# DRIVER_A.net
KiCad netlist of a schematic drawn in Altium Designer
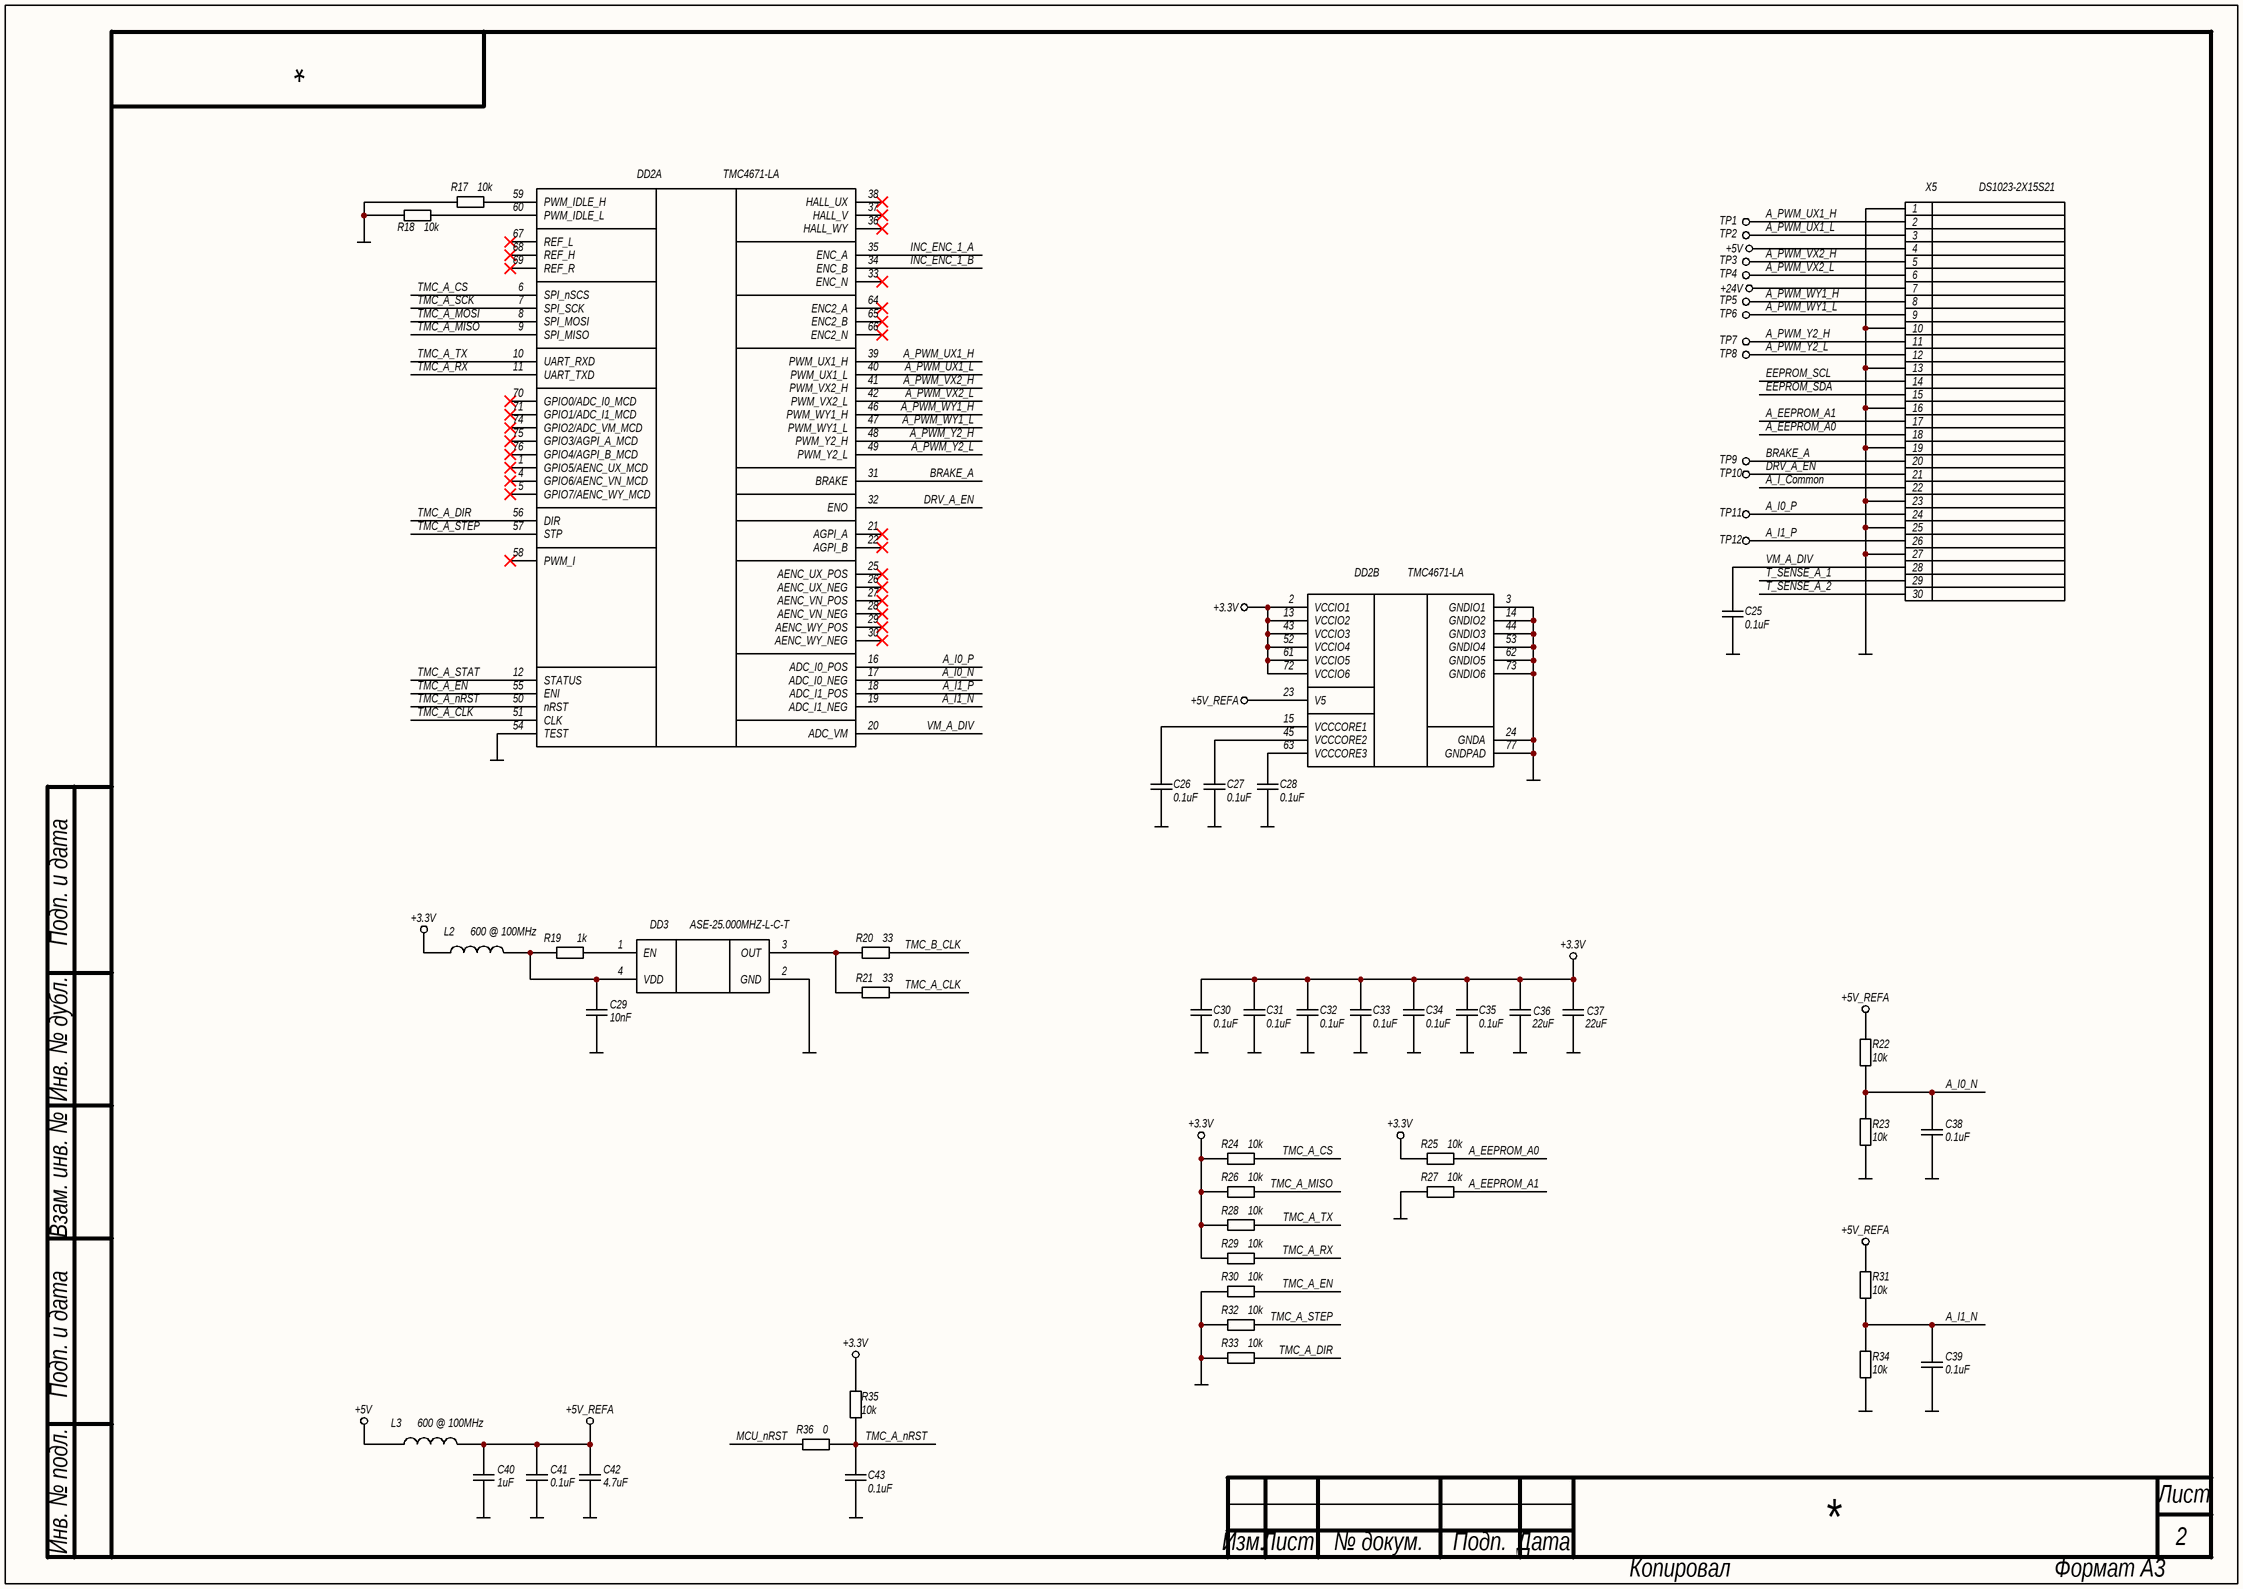
[diagram p0: DRIVER_A.SchDoc]

(export (version "E")
  (design (tool "Eeschema 10.0.6"))
  (components
    (comp (ref "C25")
      (value "0.1uF")
      (footprint "C0603N")
      (description "Конденсатор")
      (libsource (lib "Components Library") (part "CAP_FIXED"))
    )
    (comp (ref "C26")
      (value "0.1uF")
      (footprint "C0603N")
      (description "Конденсатор")
      (libsource (lib "Components Library") (part "CAP_FIXED"))
    )
    (comp (ref "C27")
      (value "0.1uF")
      (footprint "C0603N")
      (description "Конденсатор")
      (libsource (lib "Components Library") (part "CAP_FIXED"))
    )
    (comp (ref "C28")
      (value "0.1uF")
      (footprint "C0603N")
      (description "Конденсатор")
      (libsource (lib "Components Library") (part "CAP_FIXED"))
    )
    (comp (ref "C29")
      (value "10nF")
      (footprint "C0603N")
      (description "Конденсатор")
      (libsource (lib "Components Library") (part "CAP_FIXED"))
    )
    (comp (ref "C30")
      (value "0.1uF")
      (footprint "C0603N")
      (description "Конденсатор")
      (libsource (lib "Components Library") (part "CAP_FIXED"))
    )
    (comp (ref "C31")
      (value "0.1uF")
      (footprint "C0603N")
      (description "Конденсатор")
      (libsource (lib "Components Library") (part "CAP_FIXED"))
    )
    (comp (ref "C32")
      (value "0.1uF")
      (footprint "C0603N")
      (description "Конденсатор")
      (libsource (lib "Components Library") (part "CAP_FIXED"))
    )
    (comp (ref "C33")
      (value "0.1uF")
      (footprint "C0603N")
      (description "Конденсатор")
      (libsource (lib "Components Library") (part "CAP_FIXED"))
    )
    (comp (ref "C34")
      (value "0.1uF")
      (footprint "C0603N")
      (description "Конденсатор")
      (libsource (lib "Components Library") (part "CAP_FIXED"))
    )
    (comp (ref "C35")
      (value "0.1uF")
      (footprint "C0603N")
      (description "Конденсатор")
      (libsource (lib "Components Library") (part "CAP_FIXED"))
    )
    (comp (ref "C36")
      (value "22uF")
      (footprint "C0805N")
      (description "Конденсатор")
      (libsource (lib "Components Library") (part "CAP_FIXED"))
    )
    (comp (ref "C37")
      (value "22uF")
      (footprint "C0805N")
      (description "Конденсатор")
      (libsource (lib "Components Library") (part "CAP_FIXED"))
    )
    (comp (ref "C38")
      (value "0.1uF")
      (footprint "C0603N")
      (description "Конденсатор")
      (libsource (lib "Components Library") (part "CAP_FIXED"))
    )
    (comp (ref "C39")
      (value "0.1uF")
      (footprint "C0603N")
      (description "Конденсатор")
      (libsource (lib "Components Library") (part "CAP_FIXED"))
    )
    (comp (ref "C40")
      (value "1uF")
      (footprint "C0603N")
      (description "Конденсатор")
      (libsource (lib "Components Library") (part "CAP_FIXED"))
    )
    (comp (ref "C41")
      (value "0.1uF")
      (footprint "C0603N")
      (description "Конденсатор")
      (libsource (lib "Components Library") (part "CAP_FIXED"))
    )
    (comp (ref "C42")
      (value "4.7uF")
      (footprint "C0603N")
      (description "Конденсатор")
      (libsource (lib "Components Library") (part "CAP_FIXED"))
    )
    (comp (ref "C43")
      (value "0.1uF")
      (footprint "C0603N")
      (description "Конденсатор")
      (libsource (lib "Components Library") (part "CAP_FIXED"))
    )
    (comp (ref "DD2")
      (value "TMC4671-LA")
      (footprint "QFN76-EP")
      (description "Микросхема драйвер двигателя")
      (libsource (lib "Components Library") (part "TMC4671-LA"))
    )
    (comp (ref "DD3")
      (value "ASE-25.000MHZ-L-C-T")
      (footprint "ASE")
      (description "Кварцевый генератор")
      (libsource (lib "Components Library") (part "XTAL_OSC"))
    )
    (comp (ref "L2")
      (value "600 @ 100MHz")
      (footprint "FB0603N")
      (description "Фильтр ЭМП индуктивный")
      (libsource (lib "") (part "IND_FILTER_1"))
    )
    (comp (ref "L3")
      (value "600 @ 100MHz")
      (footprint "FB0603N")
      (description "Фильтр ЭМП индуктивный")
      (libsource (lib "Components Library") (part "IND_FILTER"))
    )
    (comp (ref "R17")
      (value "10k")
      (footprint "R0603N")
      (description "Резистор")
      (libsource (lib "Components Library") (part "RES_FIXED"))
    )
    (comp (ref "R18")
      (value "10k")
      (footprint "R0603N")
      (description "Резистор")
      (libsource (lib "Components Library") (part "RES_FIXED"))
    )
    (comp (ref "R19")
      (value "1k")
      (footprint "R0603N")
      (description "Резистор")
      (libsource (lib "") (part "RES_FIXED_1"))
    )
    (comp (ref "R20")
      (value "33")
      (footprint "R0603N")
      (description "Резистор")
      (libsource (lib "Components Library") (part "RES_FIXED"))
    )
    (comp (ref "R21")
      (value "33")
      (footprint "R0603N")
      (description "Резистор")
      (libsource (lib "Components Library") (part "RES_FIXED"))
    )
    (comp (ref "R22")
      (value "10k")
      (footprint "R0603N")
      (description "Резистор")
      (libsource (lib "") (part "RES_FIXED_2"))
    )
    (comp (ref "R23")
      (value "10k")
      (footprint "R0603N")
      (description "Резистор")
      (libsource (lib "") (part "RES_FIXED_2"))
    )
    (comp (ref "R24")
      (value "10k")
      (footprint "R0603N")
      (description "Резистор")
      (libsource (lib "Components Library") (part "RES_FIXED"))
    )
    (comp (ref "R25")
      (value "10k")
      (footprint "R0603N")
      (description "Резистор")
      (libsource (lib "Components Library") (part "RES_FIXED"))
    )
    (comp (ref "R26")
      (value "10k")
      (footprint "R0603N")
      (description "Резистор")
      (libsource (lib "Components Library") (part "RES_FIXED"))
    )
    (comp (ref "R27")
      (value "10k")
      (footprint "R0603N")
      (description "Резистор")
      (libsource (lib "Components Library") (part "RES_FIXED"))
    )
    (comp (ref "R28")
      (value "10k")
      (footprint "R0603N")
      (description "Резистор")
      (libsource (lib "Components Library") (part "RES_FIXED"))
    )
    (comp (ref "R29")
      (value "10k")
      (footprint "R0603N")
      (description "Резистор")
      (libsource (lib "Components Library") (part "RES_FIXED"))
    )
    (comp (ref "R30")
      (value "10k")
      (footprint "R0603N")
      (description "Резистор")
      (libsource (lib "Components Library") (part "RES_FIXED"))
    )
    (comp (ref "R31")
      (value "10k")
      (footprint "R0603N")
      (description "Резистор")
      (libsource (lib "") (part "RES_FIXED_2"))
    )
    (comp (ref "R32")
      (value "10k")
      (footprint "R0603N")
      (description "Резистор")
      (libsource (lib "Components Library") (part "RES_FIXED"))
    )
    (comp (ref "R33")
      (value "10k")
      (footprint "R0603N")
      (description "Резистор")
      (libsource (lib "Components Library") (part "RES_FIXED"))
    )
    (comp (ref "R34")
      (value "10k")
      (footprint "R0603N")
      (description "Резистор")
      (libsource (lib "") (part "RES_FIXED_2"))
    )
    (comp (ref "R35")
      (value "10k")
      (footprint "R0603N")
      (description "Резистор")
      (libsource (lib "") (part "RES_FIXED_2"))
    )
    (comp (ref "R36")
      (value "0")
      (footprint "R0603N")
      (description "Резистор")
      (libsource (lib "Components Library") (part "RES_FIXED"))
    )
    (comp (ref "TP1")
      (value "TEST_POINT")
      (footprint "TP_RPAD_0.8MM")
      (description "Контрольная точка")
      (libsource (lib "Components Library") (part "TEST_POINT"))
    )
    (comp (ref "TP2")
      (value "TEST_POINT")
      (footprint "TP_RPAD_0.8MM")
      (description "Контрольная точка")
      (libsource (lib "Components Library") (part "TEST_POINT"))
    )
    (comp (ref "TP3")
      (value "TEST_POINT")
      (footprint "TP_RPAD_0.8MM")
      (description "Контрольная точка")
      (libsource (lib "Components Library") (part "TEST_POINT"))
    )
    (comp (ref "TP4")
      (value "TEST_POINT")
      (footprint "TP_RPAD_0.8MM")
      (description "Контрольная точка")
      (libsource (lib "Components Library") (part "TEST_POINT"))
    )
    (comp (ref "TP5")
      (value "TEST_POINT")
      (footprint "TP_RPAD_0.8MM")
      (description "Контрольная точка")
      (libsource (lib "Components Library") (part "TEST_POINT"))
    )
    (comp (ref "TP6")
      (value "TEST_POINT")
      (footprint "TP_RPAD_0.8MM")
      (description "Контрольная точка")
      (libsource (lib "Components Library") (part "TEST_POINT"))
    )
    (comp (ref "TP7")
      (value "TEST_POINT")
      (footprint "TP_RPAD_0.8MM")
      (description "Контрольная точка")
      (libsource (lib "Components Library") (part "TEST_POINT"))
    )
    (comp (ref "TP8")
      (value "TEST_POINT")
      (footprint "TP_RPAD_0.8MM")
      (description "Контрольная точка")
      (libsource (lib "Components Library") (part "TEST_POINT"))
    )
    (comp (ref "TP9")
      (value "TEST_POINT")
      (footprint "TP_RPAD_0.8MM")
      (description "Контрольная точка")
      (libsource (lib "Components Library") (part "TEST_POINT"))
    )
    (comp (ref "TP10")
      (value "TEST_POINT")
      (footprint "TP_RPAD_0.8MM")
      (description "Контрольная точка")
      (libsource (lib "Components Library") (part "TEST_POINT"))
    )
    (comp (ref "TP11")
      (value "TEST_POINT")
      (footprint "TP_RPAD_0.8MM")
      (description "Контрольная точка")
      (libsource (lib "Components Library") (part "TEST_POINT"))
    )
    (comp (ref "TP12")
      (value "TEST_POINT")
      (footprint "TP_RPAD_0.8MM")
      (description "Контрольная точка")
      (libsource (lib "Components Library") (part "TEST_POINT"))
    )
    (comp (ref "X5")
      (value "DS1023-2X15S21")
      (footprint "2.54_2X15_SOCKET_HEADER")
      (description "Разъем, 30 контактов")
      (libsource (lib "Components Library") (part "Connector 30"))
    )
  )
  (nets
    (net (code "1") (name "+3.3V") (class "Default")
      (node (ref "C30") (pin "2") (pinfunction "2_2") (pintype "passive"))
      (node (ref "C31") (pin "2") (pinfunction "2_2") (pintype "passive"))
      (node (ref "C32") (pin "2") (pinfunction "2_2") (pintype "passive"))
      (node (ref "C33") (pin "2") (pinfunction "2_2") (pintype "passive"))
      (node (ref "C34") (pin "2") (pinfunction "2_2") (pintype "passive"))
      (node (ref "C35") (pin "2") (pinfunction "2_2") (pintype "passive"))
      (node (ref "C36") (pin "2") (pinfunction "2_2") (pintype "passive"))
      (node (ref "C37") (pin "2") (pinfunction "2_2") (pintype "passive"))
      (node (ref "DD2") (pin "13") (pinfunction "VCCIO2_13") (pintype "power_in"))
      (node (ref "DD2") (pin "2") (pinfunction "VCCIO1_2") (pintype "power_in"))
      (node (ref "DD2") (pin "43") (pinfunction "VCCIO3_43") (pintype "power_in"))
      (node (ref "DD2") (pin "52") (pinfunction "VCCIO4_52") (pintype "power_in"))
      (node (ref "DD2") (pin "61") (pinfunction "VCCIO5_61") (pintype "power_in"))
      (node (ref "DD2") (pin "72") (pinfunction "VCCIO6_72") (pintype "power_in"))
      (node (ref "L2") (pin "2") (pinfunction "2_2") (pintype "passive"))
      (node (ref "R24") (pin "2") (pinfunction "2_2") (pintype "passive"))
      (node (ref "R25") (pin "2") (pinfunction "2_2") (pintype "passive"))
      (node (ref "R26") (pin "2") (pinfunction "2_2") (pintype "passive"))
      (node (ref "R28") (pin "2") (pinfunction "2_2") (pintype "passive"))
      (node (ref "R29") (pin "2") (pinfunction "2_2") (pintype "passive"))
      (node (ref "R35") (pin "2") (pinfunction "2_2") (pintype "passive"))
    )
    (net (code "2") (name "+5V") (class "Default")
      (node (ref "L3") (pin "1") (pinfunction "1_1") (pintype "passive"))
      (node (ref "X5") (pin "4") (pinfunction "4_4") (pintype "power_in"))
    )
    (net (code "3") (name "+5V_REFA") (class "Default")
      (node (ref "C40") (pin "2") (pinfunction "2_2") (pintype "passive"))
      (node (ref "C41") (pin "2") (pinfunction "2_2") (pintype "passive"))
      (node (ref "C42") (pin "2") (pinfunction "2_2") (pintype "passive"))
      (node (ref "DD2") (pin "23") (pinfunction "V5_23") (pintype "power_in"))
      (node (ref "L3") (pin "2") (pinfunction "2_2") (pintype "passive"))
      (node (ref "R22") (pin "2") (pinfunction "2_2") (pintype "passive"))
      (node (ref "R31") (pin "2") (pinfunction "2_2") (pintype "passive"))
    )
    (net (code "4") (name "+24V") (class "Default")
      (node (ref "X5") (pin "7") (pinfunction "7_7") (pintype "power_in"))
    )
    (net (code "5") (name "/A_EEPROM_A0") (class "Default")
      (node (ref "R25") (pin "1") (pinfunction "1_1") (pintype "passive"))
      (node (ref "X5") (pin "18") (pinfunction "18_18") (pintype "power_in"))
    )
    (net (code "6") (name "/A_EEPROM_A1") (class "Default")
      (node (ref "R27") (pin "1") (pinfunction "1_1") (pintype "passive"))
      (node (ref "X5") (pin "17") (pinfunction "17_17") (pintype "power_in"))
    )
    (net (code "7") (name "/A_I0_N") (class "Default")
      (node (ref "C38") (pin "2") (pinfunction "2_2") (pintype "passive"))
      (node (ref "DD2") (pin "17") (pinfunction "ADC_I0_NEG_17") (pintype "power_in"))
      (node (ref "R22") (pin "1") (pinfunction "1_1") (pintype "passive"))
      (node (ref "R23") (pin "2") (pinfunction "2_2") (pintype "passive"))
    )
    (net (code "8") (name "/A_I0_P") (class "Default")
      (node (ref "DD2") (pin "16") (pinfunction "ADC_I0_POS_16") (pintype "power_in"))
      (node (ref "TP11") (pin "1") (pinfunction "1_1") (pintype "passive"))
      (node (ref "X5") (pin "24") (pinfunction "24_24") (pintype "power_in"))
    )
    (net (code "9") (name "/A_I1_N") (class "Default")
      (node (ref "C39") (pin "2") (pinfunction "2_2") (pintype "passive"))
      (node (ref "DD2") (pin "19") (pinfunction "ADC_I1_NEG_19") (pintype "power_in"))
      (node (ref "R31") (pin "1") (pinfunction "1_1") (pintype "passive"))
      (node (ref "R34") (pin "2") (pinfunction "2_2") (pintype "passive"))
    )
    (net (code "10") (name "/A_I1_P") (class "Default")
      (node (ref "DD2") (pin "18") (pinfunction "ADC_I1_POS_18") (pintype "power_in"))
      (node (ref "TP12") (pin "1") (pinfunction "1_1") (pintype "passive"))
      (node (ref "X5") (pin "26") (pinfunction "26_26") (pintype "power_in"))
    )
    (net (code "11") (name "/A_I_Common") (class "Default")
      (node (ref "X5") (pin "22") (pinfunction "22_22") (pintype "power_in"))
    )
    (net (code "12") (name "/A_PWM_UX1_H") (class "Default")
      (node (ref "DD2") (pin "39") (pinfunction "PWM_UX1_H_39") (pintype "power_in"))
      (node (ref "TP1") (pin "1") (pinfunction "1_1") (pintype "passive"))
      (node (ref "X5") (pin "2") (pinfunction "2_2") (pintype "power_in"))
    )
    (net (code "13") (name "/A_PWM_UX1_L") (class "Default")
      (node (ref "DD2") (pin "40") (pinfunction "PWM_UX1_L_40") (pintype "power_in"))
      (node (ref "TP2") (pin "1") (pinfunction "1_1") (pintype "passive"))
      (node (ref "X5") (pin "3") (pinfunction "3_3") (pintype "power_in"))
    )
    (net (code "14") (name "/A_PWM_VX2_H") (class "Default")
      (node (ref "DD2") (pin "41") (pinfunction "PWM_VX2_H_41") (pintype "power_in"))
      (node (ref "TP3") (pin "1") (pinfunction "1_1") (pintype "passive"))
      (node (ref "X5") (pin "5") (pinfunction "5_5") (pintype "power_in"))
    )
    (net (code "15") (name "/A_PWM_VX2_L") (class "Default")
      (node (ref "DD2") (pin "42") (pinfunction "PWM_VX2_L_42") (pintype "power_in"))
      (node (ref "TP4") (pin "1") (pinfunction "1_1") (pintype "passive"))
      (node (ref "X5") (pin "6") (pinfunction "6_6") (pintype "power_in"))
    )
    (net (code "16") (name "/A_PWM_WY1_H") (class "Default")
      (node (ref "DD2") (pin "46") (pinfunction "PWM_WY1_H_46") (pintype "power_in"))
      (node (ref "TP5") (pin "1") (pinfunction "1_1") (pintype "passive"))
      (node (ref "X5") (pin "8") (pinfunction "8_8") (pintype "power_in"))
    )
    (net (code "17") (name "/A_PWM_WY1_L") (class "Default")
      (node (ref "DD2") (pin "47") (pinfunction "PWM_WY1_L_47") (pintype "power_in"))
      (node (ref "TP6") (pin "1") (pinfunction "1_1") (pintype "passive"))
      (node (ref "X5") (pin "9") (pinfunction "9_9") (pintype "power_in"))
    )
    (net (code "18") (name "/A_PWM_Y2_H") (class "Default")
      (node (ref "DD2") (pin "48") (pinfunction "PWM_Y2_H_48") (pintype "power_in"))
      (node (ref "TP7") (pin "1") (pinfunction "1_1") (pintype "passive"))
      (node (ref "X5") (pin "11") (pinfunction "11_11") (pintype "power_in"))
    )
    (net (code "19") (name "/A_PWM_Y2_L") (class "Default")
      (node (ref "DD2") (pin "49") (pinfunction "PWM_Y2_L_49") (pintype "power_in"))
      (node (ref "TP8") (pin "1") (pinfunction "1_1") (pintype "passive"))
      (node (ref "X5") (pin "12") (pinfunction "12_12") (pintype "power_in"))
    )
    (net (code "20") (name "/BRAKE_A") (class "Default")
      (node (ref "DD2") (pin "31") (pinfunction "BRAKE_31") (pintype "power_in"))
      (node (ref "TP9") (pin "1") (pinfunction "1_1") (pintype "passive"))
      (node (ref "X5") (pin "20") (pinfunction "20_20") (pintype "power_in"))
    )
    (net (code "21") (name "/DRV_A_EN") (class "Default")
      (node (ref "DD2") (pin "32") (pinfunction "ENO_32") (pintype "power_in"))
      (node (ref "TP10") (pin "1") (pinfunction "1_1") (pintype "passive"))
      (node (ref "X5") (pin "21") (pinfunction "21_21") (pintype "power_in"))
    )
    (net (code "22") (name "/EEPROM_SCL") (class "Default")
      (node (ref "X5") (pin "14") (pinfunction "14_14") (pintype "power_in"))
    )
    (net (code "23") (name "/EEPROM_SDA") (class "Default")
      (node (ref "X5") (pin "15") (pinfunction "15_15") (pintype "power_in"))
    )
    (net (code "24") (name "/INC_ENC_1_A") (class "Default")
      (node (ref "DD2") (pin "35") (pinfunction "ENC_A_35") (pintype "power_in"))
    )
    (net (code "25") (name "/INC_ENC_1_B") (class "Default")
      (node (ref "DD2") (pin "34") (pinfunction "ENC_B_34") (pintype "power_in"))
    )
    (net (code "26") (name "/MCU_nRST") (class "Default")
      (node (ref "R36") (pin "2") (pinfunction "2_2") (pintype "passive"))
    )
    (net (code "27") (name "/TMC_A_CLK") (class "Default")
      (node (ref "DD2") (pin "51") (pinfunction "CLK_51") (pintype "power_in"))
      (node (ref "R21") (pin "1") (pinfunction "1_1") (pintype "passive"))
    )
    (net (code "28") (name "/TMC_A_CS") (class "Default")
      (node (ref "DD2") (pin "6") (pinfunction "SPI_nSCS_6") (pintype "power_in"))
      (node (ref "R24") (pin "1") (pinfunction "1_1") (pintype "passive"))
    )
    (net (code "29") (name "/TMC_A_DIR") (class "Default")
      (node (ref "DD2") (pin "56") (pinfunction "DIR_56") (pintype "power_in"))
      (node (ref "R33") (pin "1") (pinfunction "1_1") (pintype "passive"))
    )
    (net (code "30") (name "/TMC_A_EN") (class "Default")
      (node (ref "DD2") (pin "55") (pinfunction "ENI_55") (pintype "power_in"))
      (node (ref "R30") (pin "1") (pinfunction "1_1") (pintype "passive"))
    )
    (net (code "31") (name "/TMC_A_MISO") (class "Default")
      (node (ref "DD2") (pin "9") (pinfunction "SPI_MISO_9") (pintype "power_in"))
      (node (ref "R26") (pin "1") (pinfunction "1_1") (pintype "passive"))
    )
    (net (code "32") (name "/TMC_A_MOSI") (class "Default")
      (node (ref "DD2") (pin "8") (pinfunction "SPI_MOSI_8") (pintype "power_in"))
    )
    (net (code "33") (name "/TMC_A_RX") (class "Default")
      (node (ref "DD2") (pin "11") (pinfunction "UART_TXD_11") (pintype "power_in"))
      (node (ref "R29") (pin "1") (pinfunction "1_1") (pintype "passive"))
    )
    (net (code "34") (name "/TMC_A_SCK") (class "Default")
      (node (ref "DD2") (pin "7") (pinfunction "SPI_SCK_7") (pintype "power_in"))
    )
    (net (code "35") (name "/TMC_A_STAT") (class "Default")
      (node (ref "DD2") (pin "12") (pinfunction "STATUS_12") (pintype "power_in"))
    )
    (net (code "36") (name "/TMC_A_STEP") (class "Default")
      (node (ref "DD2") (pin "57") (pinfunction "STP_57") (pintype "power_in"))
      (node (ref "R32") (pin "1") (pinfunction "1_1") (pintype "passive"))
    )
    (net (code "37") (name "/TMC_A_TX") (class "Default")
      (node (ref "DD2") (pin "10") (pinfunction "UART_RXD_10") (pintype "power_in"))
      (node (ref "R28") (pin "1") (pinfunction "1_1") (pintype "passive"))
    )
    (net (code "38") (name "/TMC_A_nRST") (class "Default")
      (node (ref "C43") (pin "2") (pinfunction "2_2") (pintype "passive"))
      (node (ref "DD2") (pin "50") (pinfunction "nRST_50") (pintype "power_in"))
      (node (ref "R35") (pin "1") (pinfunction "1_1") (pintype "passive"))
      (node (ref "R36") (pin "1") (pinfunction "1_1") (pintype "passive"))
    )
    (net (code "39") (name "/TMC_B_CLK") (class "Default")
      (node (ref "R20") (pin "1") (pinfunction "1_1") (pintype "passive"))
    )
    (net (code "40") (name "/T_SENSE_A_1") (class "Default")
      (node (ref "X5") (pin "29") (pinfunction "29_29") (pintype "power_in"))
    )
    (net (code "41") (name "/T_SENSE_A_2") (class "Default")
      (node (ref "X5") (pin "30") (pinfunction "30_30") (pintype "power_in"))
    )
    (net (code "42") (name "/VM_A_DIV") (class "Default")
      (node (ref "C25") (pin "2") (pinfunction "2_2") (pintype "passive"))
      (node (ref "DD2") (pin "20") (pinfunction "ADC_VM_20") (pintype "power_in"))
      (node (ref "X5") (pin "28") (pinfunction "28_28") (pintype "power_in"))
    )
    (net (code "43") (name "GND") (class "Default")
      (node (ref "C25") (pin "1") (pinfunction "1_1") (pintype "passive"))
      (node (ref "C26") (pin "1") (pinfunction "1_1") (pintype "passive"))
      (node (ref "C27") (pin "1") (pinfunction "1_1") (pintype "passive"))
      (node (ref "C28") (pin "1") (pinfunction "1_1") (pintype "passive"))
      (node (ref "C29") (pin "2") (pinfunction "2_2") (pintype "passive"))
      (node (ref "C30") (pin "1") (pinfunction "1_1") (pintype "passive"))
      (node (ref "C31") (pin "1") (pinfunction "1_1") (pintype "passive"))
      (node (ref "C32") (pin "1") (pinfunction "1_1") (pintype "passive"))
      (node (ref "C33") (pin "1") (pinfunction "1_1") (pintype "passive"))
      (node (ref "C34") (pin "1") (pinfunction "1_1") (pintype "passive"))
      (node (ref "C35") (pin "1") (pinfunction "1_1") (pintype "passive"))
      (node (ref "C36") (pin "1") (pinfunction "1_1") (pintype "passive"))
      (node (ref "C37") (pin "1") (pinfunction "1_1") (pintype "passive"))
      (node (ref "C38") (pin "1") (pinfunction "1_1") (pintype "passive"))
      (node (ref "C39") (pin "1") (pinfunction "1_1") (pintype "passive"))
      (node (ref "C40") (pin "1") (pinfunction "1_1") (pintype "passive"))
      (node (ref "C41") (pin "1") (pinfunction "1_1") (pintype "passive"))
      (node (ref "C42") (pin "1") (pinfunction "1_1") (pintype "passive"))
      (node (ref "C43") (pin "1") (pinfunction "1_1") (pintype "passive"))
      (node (ref "DD2") (pin "14") (pinfunction "GNDIO2_14") (pintype "power_in"))
      (node (ref "DD2") (pin "24") (pinfunction "GNDA_24") (pintype "power_in"))
      (node (ref "DD2") (pin "3") (pinfunction "GNDIO1_3") (pintype "power_in"))
      (node (ref "DD2") (pin "44") (pinfunction "GNDIO3_44") (pintype "power_in"))
      (node (ref "DD2") (pin "53") (pinfunction "GNDIO4_53") (pintype "power_in"))
      (node (ref "DD2") (pin "54") (pinfunction "TEST_54") (pintype "power_in"))
      (node (ref "DD2") (pin "62") (pinfunction "GNDIO5_62") (pintype "power_in"))
      (node (ref "DD2") (pin "73") (pinfunction "GNDIO6_73") (pintype "power_in"))
      (node (ref "DD2") (pin "77") (pinfunction "GNDPAD_77") (pintype "power_in"))
      (node (ref "DD3") (pin "2") (pinfunction "GND_2") (pintype "power_in"))
      (node (ref "R17") (pin "2") (pinfunction "2_2") (pintype "passive"))
      (node (ref "R18") (pin "2") (pinfunction "2_2") (pintype "passive"))
      (node (ref "R23") (pin "1") (pinfunction "1_1") (pintype "passive"))
      (node (ref "R27") (pin "2") (pinfunction "2_2") (pintype "passive"))
      (node (ref "R30") (pin "2") (pinfunction "2_2") (pintype "passive"))
      (node (ref "R32") (pin "2") (pinfunction "2_2") (pintype "passive"))
      (node (ref "R33") (pin "2") (pinfunction "2_2") (pintype "passive"))
      (node (ref "R34") (pin "1") (pinfunction "1_1") (pintype "passive"))
      (node (ref "X5") (pin "1") (pinfunction "1_1") (pintype "power_in"))
      (node (ref "X5") (pin "10") (pinfunction "10_10") (pintype "power_in"))
      (node (ref "X5") (pin "13") (pinfunction "13_13") (pintype "power_in"))
      (node (ref "X5") (pin "16") (pinfunction "16_16") (pintype "power_in"))
      (node (ref "X5") (pin "19") (pinfunction "19_19") (pintype "power_in"))
      (node (ref "X5") (pin "23") (pinfunction "23_23") (pintype "power_in"))
      (node (ref "X5") (pin "25") (pinfunction "25_25") (pintype "power_in"))
      (node (ref "X5") (pin "27") (pinfunction "27_27") (pintype "power_in"))
    )
    (net (code "44") (name "Net-(DD2A-PWM_IDLE_H)") (class "Default")
      (node (ref "DD2") (pin "59") (pinfunction "PWM_IDLE_H_59") (pintype "power_in"))
      (node (ref "R17") (pin "1") (pinfunction "1_1") (pintype "passive"))
    )
    (net (code "45") (name "Net-(DD2A-PWM_IDLE_L)") (class "Default")
      (node (ref "DD2") (pin "60") (pinfunction "PWM_IDLE_L_60") (pintype "power_in"))
      (node (ref "R18") (pin "1") (pinfunction "1_1") (pintype "passive"))
    )
    (net (code "46") (name "Net-(DD2B-VCCCORE1)") (class "Default")
      (node (ref "C26") (pin "2") (pinfunction "2_2") (pintype "passive"))
      (node (ref "DD2") (pin "15") (pinfunction "VCCCORE1_15") (pintype "power_in"))
    )
    (net (code "47") (name "Net-(DD2B-VCCCORE2)") (class "Default")
      (node (ref "C27") (pin "2") (pinfunction "2_2") (pintype "passive"))
      (node (ref "DD2") (pin "45") (pinfunction "VCCCORE2_45") (pintype "power_in"))
    )
    (net (code "48") (name "Net-(DD2B-VCCCORE3)") (class "Default")
      (node (ref "C28") (pin "2") (pinfunction "2_2") (pintype "passive"))
      (node (ref "DD2") (pin "63") (pinfunction "VCCCORE3_63") (pintype "power_in"))
    )
    (net (code "49") (name "Net-(DD3-EN)") (class "Default")
      (node (ref "DD3") (pin "1") (pinfunction "EN_1") (pintype "power_in"))
      (node (ref "R19") (pin "2") (pinfunction "2_2") (pintype "passive"))
    )
    (net (code "50") (name "Net-(DD3-OUT)") (class "Default")
      (node (ref "DD3") (pin "3") (pinfunction "OUT_3") (pintype "power_in"))
      (node (ref "R20") (pin "2") (pinfunction "2_2") (pintype "passive"))
      (node (ref "R21") (pin "2") (pinfunction "2_2") (pintype "passive"))
    )
    (net (code "51") (name "Net-(DD3-VDD)") (class "Default")
      (node (ref "C29") (pin "1") (pinfunction "1_1") (pintype "passive"))
      (node (ref "DD3") (pin "4") (pinfunction "VDD_4") (pintype "power_in"))
      (node (ref "L2") (pin "1") (pinfunction "1_1") (pintype "passive"))
      (node (ref "R19") (pin "1") (pinfunction "1_1") (pintype "passive"))
    )
    (net (code "52") (name "unconnected-(DD2A-AENC_UX_NEG-Pad26)") (class "Default")
      (node (ref "DD2") (pin "26") (pinfunction "AENC_UX_NEG_26") (pintype "power_in+no_connect"))
    )
    (net (code "53") (name "unconnected-(DD2A-AENC_UX_POS-Pad25)") (class "Default")
      (node (ref "DD2") (pin "25") (pinfunction "AENC_UX_POS_25") (pintype "power_in+no_connect"))
    )
    (net (code "54") (name "unconnected-(DD2A-AENC_VN_NEG-Pad28)") (class "Default")
      (node (ref "DD2") (pin "28") (pinfunction "AENC_VN_NEG_28") (pintype "power_in+no_connect"))
    )
    (net (code "55") (name "unconnected-(DD2A-AENC_VN_POS-Pad27)") (class "Default")
      (node (ref "DD2") (pin "27") (pinfunction "AENC_VN_POS_27") (pintype "power_in+no_connect"))
    )
    (net (code "56") (name "unconnected-(DD2A-AENC_WY_NEG-Pad30)") (class "Default")
      (node (ref "DD2") (pin "30") (pinfunction "AENC_WY_NEG_30") (pintype "power_in+no_connect"))
    )
    (net (code "57") (name "unconnected-(DD2A-AENC_WY_POS-Pad29)") (class "Default")
      (node (ref "DD2") (pin "29") (pinfunction "AENC_WY_POS_29") (pintype "power_in+no_connect"))
    )
    (net (code "58") (name "unconnected-(DD2A-AGPI_A-Pad21)") (class "Default")
      (node (ref "DD2") (pin "21") (pinfunction "AGPI_A_21") (pintype "power_in+no_connect"))
    )
    (net (code "59") (name "unconnected-(DD2A-AGPI_B-Pad22)") (class "Default")
      (node (ref "DD2") (pin "22") (pinfunction "AGPI_B_22") (pintype "power_in+no_connect"))
    )
    (net (code "60") (name "unconnected-(DD2A-ENC2_A-Pad64)") (class "Default")
      (node (ref "DD2") (pin "64") (pinfunction "ENC2_A_64") (pintype "power_in+no_connect"))
    )
    (net (code "61") (name "unconnected-(DD2A-ENC2_B-Pad65)") (class "Default")
      (node (ref "DD2") (pin "65") (pinfunction "ENC2_B_65") (pintype "power_in+no_connect"))
    )
    (net (code "62") (name "unconnected-(DD2A-ENC2_N-Pad66)") (class "Default")
      (node (ref "DD2") (pin "66") (pinfunction "ENC2_N_66") (pintype "power_in+no_connect"))
    )
    (net (code "63") (name "unconnected-(DD2A-ENC_N-Pad33)") (class "Default")
      (node (ref "DD2") (pin "33") (pinfunction "ENC_N_33") (pintype "power_in+no_connect"))
    )
    (net (code "64") (name "unconnected-(DD2A-GPIO0{slash}ADC_I0_MCD-Pad70)") (class "Default")
      (node (ref "DD2") (pin "70") (pinfunction "GPIO0/ADC_I0_MCD_70") (pintype "power_in+no_connect"))
    )
    (net (code "65") (name "unconnected-(DD2A-GPIO1{slash}ADC_I1_MCD-Pad71)") (class "Default")
      (node (ref "DD2") (pin "71") (pinfunction "GPIO1/ADC_I1_MCD_71") (pintype "power_in+no_connect"))
    )
    (net (code "66") (name "unconnected-(DD2A-GPIO2{slash}ADC_VM_MCD-Pad74)") (class "Default")
      (node (ref "DD2") (pin "74") (pinfunction "GPIO2/ADC_VM_MCD_74") (pintype "power_in+no_connect"))
    )
    (net (code "67") (name "unconnected-(DD2A-GPIO3{slash}AGPI_A_MCD-Pad75)") (class "Default")
      (node (ref "DD2") (pin "75") (pinfunction "GPIO3/AGPI_A_MCD_75") (pintype "power_in+no_connect"))
    )
    (net (code "68") (name "unconnected-(DD2A-GPIO4{slash}AGPI_B_MCD-Pad76)") (class "Default")
      (node (ref "DD2") (pin "76") (pinfunction "GPIO4/AGPI_B_MCD_76") (pintype "power_in+no_connect"))
    )
    (net (code "69") (name "unconnected-(DD2A-GPIO5{slash}AENC_UX_MCD-Pad1)") (class "Default")
      (node (ref "DD2") (pin "1") (pinfunction "GPIO5/AENC_UX_MCD_1") (pintype "power_in+no_connect"))
    )
    (net (code "70") (name "unconnected-(DD2A-GPIO6{slash}AENC_VN_MCD-Pad4)") (class "Default")
      (node (ref "DD2") (pin "4") (pinfunction "GPIO6/AENC_VN_MCD_4") (pintype "power_in+no_connect"))
    )
    (net (code "71") (name "unconnected-(DD2A-GPIO7{slash}AENC_WY_MCD-Pad5)") (class "Default")
      (node (ref "DD2") (pin "5") (pinfunction "GPIO7/AENC_WY_MCD_5") (pintype "power_in+no_connect"))
    )
    (net (code "72") (name "unconnected-(DD2A-HALL_UX-Pad38)") (class "Default")
      (node (ref "DD2") (pin "38") (pinfunction "HALL_UX_38") (pintype "power_in+no_connect"))
    )
    (net (code "73") (name "unconnected-(DD2A-HALL_V-Pad37)") (class "Default")
      (node (ref "DD2") (pin "37") (pinfunction "HALL_V_37") (pintype "power_in+no_connect"))
    )
    (net (code "74") (name "unconnected-(DD2A-HALL_WY-Pad36)") (class "Default")
      (node (ref "DD2") (pin "36") (pinfunction "HALL_WY_36") (pintype "power_in+no_connect"))
    )
    (net (code "75") (name "unconnected-(DD2A-PWM_I-Pad58)") (class "Default")
      (node (ref "DD2") (pin "58") (pinfunction "PWM_I_58") (pintype "power_in+no_connect"))
    )
    (net (code "76") (name "unconnected-(DD2A-REF_H-Pad68)") (class "Default")
      (node (ref "DD2") (pin "68") (pinfunction "REF_H_68") (pintype "power_in+no_connect"))
    )
    (net (code "77") (name "unconnected-(DD2A-REF_L-Pad67)") (class "Default")
      (node (ref "DD2") (pin "67") (pinfunction "REF_L_67") (pintype "power_in+no_connect"))
    )
    (net (code "78") (name "unconnected-(DD2A-REF_R-Pad69)") (class "Default")
      (node (ref "DD2") (pin "69") (pinfunction "REF_R_69") (pintype "power_in+no_connect"))
    )
  )
)
